# AFE.net
KiCad netlist of a schematic drawn in Altium Designer
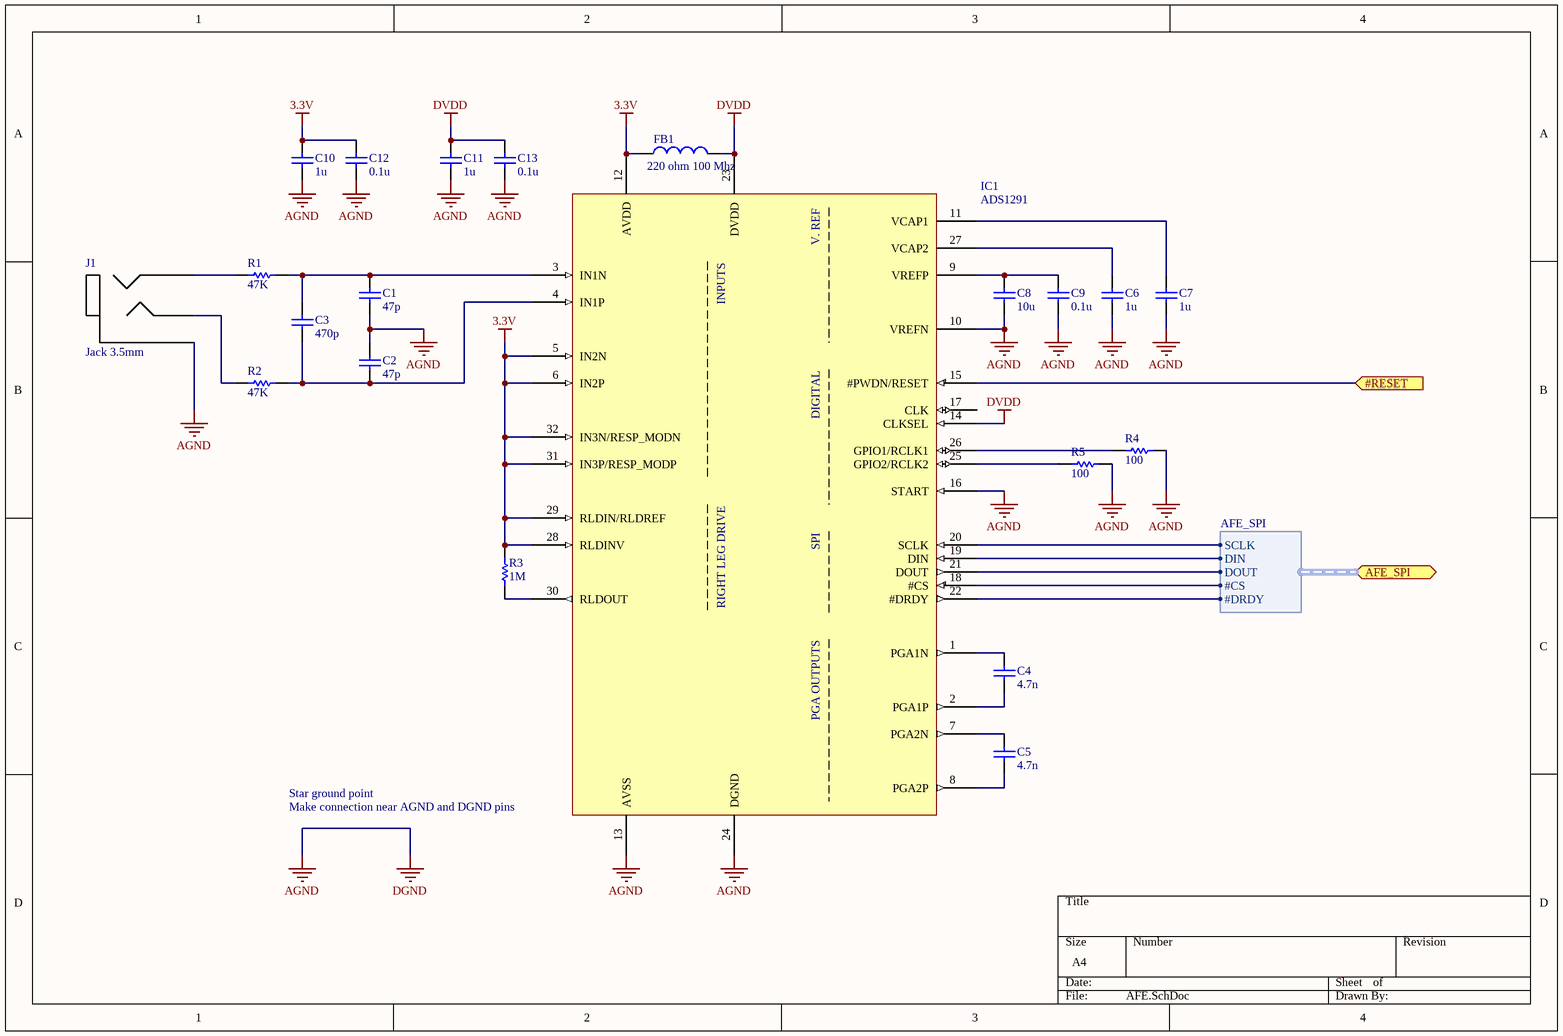
[diagram p0: AFE.SchDoc]

(export (version "E")
  (design (tool "Eeschema 10.0.6"))
  (components
    (comp (ref "C1") (value "47p") (footprint "0805 CAP") (libsource (lib "B105lib") (part "Cap")))
    (comp (ref "C2") (value "47p") (footprint "0805 CAP") (libsource (lib "B105lib") (part "Cap")))
    (comp (ref "C3") (value "470p") (footprint "0805 CAP") (libsource (lib "B105lib") (part "Cap")))
    (comp (ref "C4") (value "4.7n") (footprint "0805 CAP") (libsource (lib "B105lib") (part "Cap")))
    (comp (ref "C5") (value "4.7n") (footprint "0805 CAP") (libsource (lib "B105lib") (part "Cap")))
    (comp (ref "C6") (value "1u") (footprint "0805 CAP") (libsource (lib "B105lib") (part "Cap")))
    (comp (ref "C7") (value "1u") (footprint "0805 CAP") (libsource (lib "B105lib") (part "Cap")))
    (comp (ref "C8") (value "10u") (footprint "0805 CAP") (libsource (lib "B105lib") (part "Cap")))
    (comp (ref "C9") (value "0.1u") (footprint "0805 CAP") (libsource (lib "B105lib") (part "Cap")))
    (comp (ref "C10") (value "1u") (footprint "0805 CAP") (libsource (lib "B105lib") (part "Cap")))
    (comp (ref "C11") (value "1u") (footprint "0805 CAP") (libsource (lib "B105lib") (part "Cap")))
    (comp (ref "C12") (value "0.1u") (footprint "0805 CAP") (libsource (lib "B105lib") (part "Cap")))
    (comp (ref "C13") (value "0.1u") (footprint "0805 CAP") (libsource (lib "B105lib") (part "Cap")))
    (comp (ref "FB1")
      (value "220 ohm 100 Mhz")
      (footprint "0805 Ind")
      (description "INDUCTOR, 0.04OHM, 3A, 0805")
      (libsource (lib "B105lib") (part "Ferrita"))
    )
    (comp (ref "IC1")
      (value "ADS1291")
      (footprint "TSQFP50P700X700X120-32N")
      (libsource (lib "ECG_EMG") (part "ADS1291"))
    )
    (comp (ref "J1")
      (value "Jack 3.5mm")
      (footprint "Jack 3.5mm")
      (libsource (lib "ECG_EMG") (part "Jack 3.5mm"))
    )
    (comp (ref "R1") (value "47K") (footprint "0805 Res") (libsource (lib "B105lib") (part "Res")))
    (comp (ref "R2") (value "47K") (footprint "0805 Res") (libsource (lib "B105lib") (part "Res")))
    (comp (ref "R3") (value "1M") (footprint "0805 Res") (libsource (lib "B105lib") (part "Res")))
    (comp (ref "R4") (value "100") (footprint "0805 Res") (libsource (lib "B105lib") (part "Res")))
    (comp (ref "R5") (value "100") (footprint "0805 Res") (libsource (lib "B105lib") (part "Res")))
  )
  (nets
    (net (code "2") (name "/#CS") (class "Default")
      (node (ref "IC1") (pin "18") (pinfunction "#CS_18") (pintype "input"))
    )
    (net (code "3") (name "/#DRDY") (class "Default")
      (node (ref "IC1") (pin "22") (pinfunction "#DRDY_22") (pintype "output"))
    )
    (net (code "4") (name "/#RESET") (class "Default")
      (node (ref "IC1") (pin "15") (pinfunction "#PWDN/RESET_15") (pintype "input"))
    )
    (net (code "5") (name "/DIN") (class "Default")
      (node (ref "IC1") (pin "19") (pinfunction "DIN_19") (pintype "input"))
    )
    (net (code "6") (name "/DOUT") (class "Default")
      (node (ref "IC1") (pin "21") (pinfunction "DOUT_21") (pintype "output"))
    )
    (net (code "7") (name "/SCLK") (class "Default")
      (node (ref "IC1") (pin "20") (pinfunction "SCLK_20") (pintype "input"))
    )
    (net (code "9") (name "3.3V") (class "Default")
      (node (ref "C10") (pin "2") (pinfunction "2_2") (pintype "passive"))
      (node (ref "C12") (pin "2") (pinfunction "2_2") (pintype "passive"))
      (node (ref "FB1") (pin "1") (pinfunction "1_1") (pintype "passive"))
      (node (ref "IC1") (pin "12") (pinfunction "AVDD_12") (pintype "power_in"))
      (node (ref "IC1") (pin "28") (pinfunction "RLDINV_28") (pintype "input"))
      (node (ref "IC1") (pin "29") (pinfunction "RLDIN/RLDREF_29") (pintype "input"))
      (node (ref "IC1") (pin "31") (pinfunction "IN3P/RESP_MODP_31") (pintype "input"))
      (node (ref "IC1") (pin "32") (pinfunction "IN3N/RESP_MODN_32") (pintype "input"))
      (node (ref "IC1") (pin "5") (pinfunction "IN2N_5") (pintype "input"))
      (node (ref "IC1") (pin "6") (pinfunction "IN2P_6") (pintype "input"))
      (node (ref "R3") (pin "2") (pinfunction "2_2") (pintype "passive"))
    )
    (net (code "10") (name "AGND") (class "Default")
      (node (ref "C1") (pin "1") (pinfunction "1_1") (pintype "passive"))
      (node (ref "C10") (pin "1") (pinfunction "1_1") (pintype "passive"))
      (node (ref "C11") (pin "1") (pinfunction "1_1") (pintype "passive"))
      (node (ref "C12") (pin "1") (pinfunction "1_1") (pintype "passive"))
      (node (ref "C13") (pin "1") (pinfunction "1_1") (pintype "passive"))
      (node (ref "C2") (pin "2") (pinfunction "2_2") (pintype "passive"))
      (node (ref "C6") (pin "1") (pinfunction "1_1") (pintype "passive"))
      (node (ref "C7") (pin "1") (pinfunction "1_1") (pintype "passive"))
      (node (ref "C8") (pin "1") (pinfunction "1_1") (pintype "passive"))
      (node (ref "C9") (pin "1") (pinfunction "1_1") (pintype "passive"))
      (node (ref "IC1") (pin "10") (pinfunction "VREFN_10") (pintype "passive"))
      (node (ref "IC1") (pin "13") (pinfunction "AVSS_13") (pintype "power_in"))
      (node (ref "IC1") (pin "16") (pinfunction "START_16") (pintype "input"))
      (node (ref "IC1") (pin "24") (pinfunction "DGND_24") (pintype "power_in"))
      (node (ref "J1") (pin "1") (pinfunction "Sleeve_1") (pintype "passive"))
      (node (ref "R4") (pin "1") (pinfunction "1_1") (pintype "passive"))
      (node (ref "R5") (pin "1") (pinfunction "1_1") (pintype "passive"))
    )
    (net (code "11") (name "DVDD") (class "Default")
      (node (ref "C11") (pin "2") (pinfunction "2_2") (pintype "passive"))
      (node (ref "C13") (pin "2") (pinfunction "2_2") (pintype "passive"))
      (node (ref "FB1") (pin "2") (pinfunction "2_2") (pintype "passive"))
      (node (ref "IC1") (pin "14") (pinfunction "CLKSEL_14") (pintype "input"))
      (node (ref "IC1") (pin "23") (pinfunction "DVDD_23") (pintype "power_in"))
    )
    (net (code "12") (name "Net-(IC1-GPIO1{slash}RCLK1)") (class "Default")
      (node (ref "IC1") (pin "26") (pinfunction "GPIO1/RCLK1_26") (pintype "bidirectional"))
      (node (ref "R4") (pin "2") (pinfunction "2_2") (pintype "passive"))
    )
    (net (code "13") (name "Net-(IC1-GPIO2{slash}RCLK2)") (class "Default")
      (node (ref "IC1") (pin "25") (pinfunction "GPIO2/RCLK2_25") (pintype "bidirectional"))
      (node (ref "R5") (pin "2") (pinfunction "2_2") (pintype "passive"))
    )
    (net (code "14") (name "Net-(IC1-IN1N)") (class "Default")
      (node (ref "C1") (pin "2") (pinfunction "2_2") (pintype "passive"))
      (node (ref "C3") (pin "2") (pinfunction "2_2") (pintype "passive"))
      (node (ref "IC1") (pin "3") (pinfunction "IN1N_3") (pintype "input"))
      (node (ref "R1") (pin "2") (pinfunction "2_2") (pintype "passive"))
    )
    (net (code "15") (name "Net-(IC1-IN1P)") (class "Default")
      (node (ref "C2") (pin "1") (pinfunction "1_1") (pintype "passive"))
      (node (ref "C3") (pin "1") (pinfunction "1_1") (pintype "passive"))
      (node (ref "IC1") (pin "4") (pinfunction "IN1P_4") (pintype "input"))
      (node (ref "R2") (pin "2") (pinfunction "2_2") (pintype "passive"))
    )
    (net (code "16") (name "Net-(IC1-PGA1N)") (class "Default")
      (node (ref "C4") (pin "2") (pinfunction "2_2") (pintype "passive"))
      (node (ref "IC1") (pin "1") (pinfunction "PGA1N_1") (pintype "output"))
    )
    (net (code "17") (name "Net-(IC1-PGA1P)") (class "Default")
      (node (ref "C4") (pin "1") (pinfunction "1_1") (pintype "passive"))
      (node (ref "IC1") (pin "2") (pinfunction "PGA1P_2") (pintype "output"))
    )
    (net (code "18") (name "Net-(IC1-PGA2N)") (class "Default")
      (node (ref "C5") (pin "2") (pinfunction "2_2") (pintype "passive"))
      (node (ref "IC1") (pin "7") (pinfunction "PGA2N_7") (pintype "output"))
    )
    (net (code "19") (name "Net-(IC1-PGA2P)") (class "Default")
      (node (ref "C5") (pin "1") (pinfunction "1_1") (pintype "passive"))
      (node (ref "IC1") (pin "8") (pinfunction "PGA2P_8") (pintype "output"))
    )
    (net (code "20") (name "Net-(IC1-RLDOUT)") (class "Default")
      (node (ref "IC1") (pin "30") (pinfunction "RLDOUT_30") (pintype "output"))
      (node (ref "R3") (pin "1") (pinfunction "1_1") (pintype "passive"))
    )
    (net (code "21") (name "Net-(IC1-VCAP1)") (class "Default")
      (node (ref "C7") (pin "2") (pinfunction "2_2") (pintype "passive"))
      (node (ref "IC1") (pin "11") (pinfunction "VCAP1_11") (pintype "passive"))
    )
    (net (code "22") (name "Net-(IC1-VCAP2)") (class "Default")
      (node (ref "C6") (pin "2") (pinfunction "2_2") (pintype "passive"))
      (node (ref "IC1") (pin "27") (pinfunction "VCAP2_27") (pintype "passive"))
    )
    (net (code "23") (name "Net-(IC1-VREFP)") (class "Default")
      (node (ref "C8") (pin "2") (pinfunction "2_2") (pintype "passive"))
      (node (ref "C9") (pin "2") (pinfunction "2_2") (pintype "passive"))
      (node (ref "IC1") (pin "9") (pinfunction "VREFP_9") (pintype "passive"))
    )
    (net (code "24") (name "Net-(J1-Ring)") (class "Default")
      (node (ref "J1") (pin "3") (pinfunction "Ring_3") (pintype "passive"))
      (node (ref "R1") (pin "1") (pinfunction "1_1") (pintype "passive"))
    )
    (net (code "25") (name "Net-(J1-Tip)") (class "Default")
      (node (ref "J1") (pin "2") (pinfunction "Tip_2") (pintype "passive"))
      (node (ref "R2") (pin "1") (pinfunction "1_1") (pintype "passive"))
    )
    (net (code "26") (name "unconnected-(IC1-CLK-Pad17)") (class "Default")
      (node (ref "IC1") (pin "17") (pinfunction "CLK_17") (pintype "bidirectional"))
    )
  )
)
